# attiny1634_bo.net
KiCad netlist of a schematic drawn in EAGLE
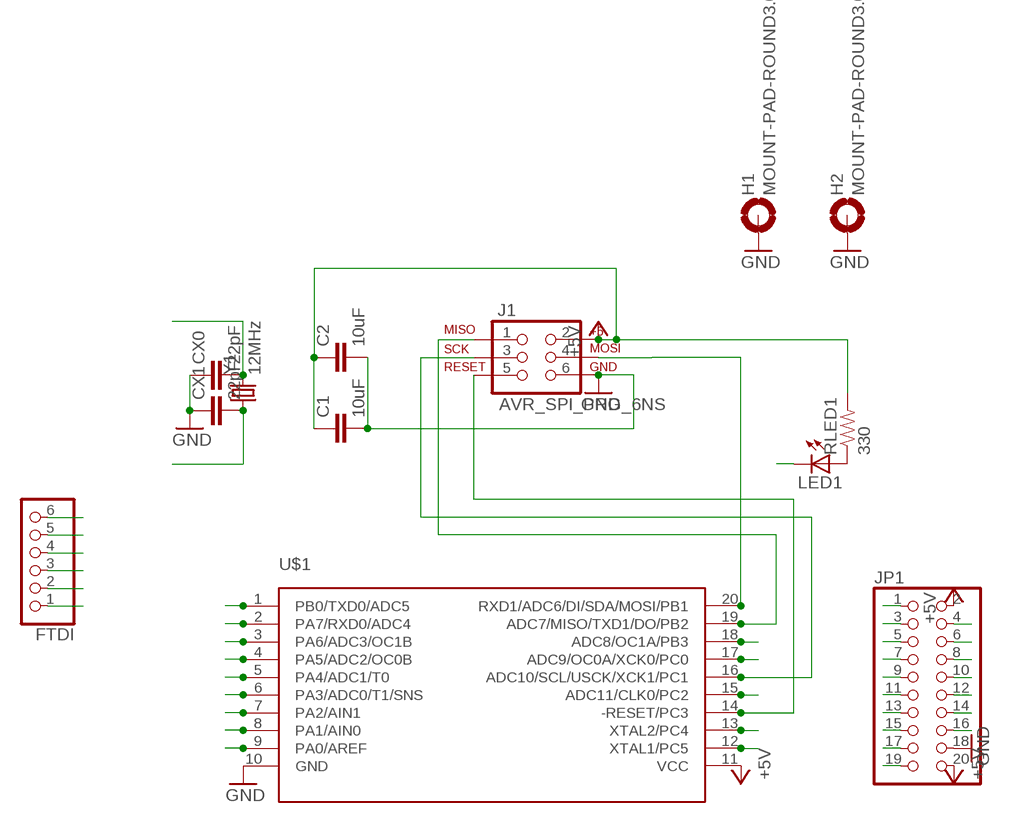
[diagram p0: schematic, sheet 1]

(export (version "E")
  (design (tool "Eeschema 10.0.6"))
  (components
    (comp (ref "C1")
      (value "10uF")
      (footprint "eagle-import:C0805")
      (libsource (lib "eagle-import") (part "C-EUC0805"))
    )
    (comp (ref "C2")
      (value "10uF")
      (footprint "eagle-import:C0805")
      (libsource (lib "eagle-import") (part "C-EUC0805"))
    )
    (comp (ref "CX0")
      (value "22pF")
      (footprint "eagle-import:C0603")
      (libsource (lib "eagle-import") (part "C-EUC0603"))
    )
    (comp (ref "CX1")
      (value "22pF")
      (footprint "eagle-import:C0603")
      (libsource (lib "eagle-import") (part "C-EUC0603"))
    )
    (comp (ref "FTDI")
      (value "PINHD-1X6")
      (footprint "eagle-import:1X06")
      (libsource (lib "eagle-import") (part "PINHD-1X6"))
    )
    (comp (ref "H1")
      (value "MOUNT-PAD-ROUND3.0")
      (footprint "eagle-import:3,0-PAD")
      (libsource (lib "eagle-import") (part "MOUNT-PAD-ROUND3.0"))
    )
    (comp (ref "H2")
      (value "MOUNT-PAD-ROUND3.0")
      (footprint "eagle-import:3,0-PAD")
      (libsource (lib "eagle-import") (part "MOUNT-PAD-ROUND3.0"))
    )
    (comp (ref "J1")
      (value "AVR_SPI_PRG_6NS")
      (footprint "eagle-import:2X3-NS")
      (libsource (lib "eagle-import") (part "AVR_SPI_PRG_6NS"))
    )
    (comp (ref "JP1")
      (value "PINHD-2X10")
      (footprint "eagle-import:2X10")
      (libsource (lib "eagle-import") (part "PINHD-2X10"))
    )
    (comp (ref "LED1")
      (value "LED0603")
      (footprint "eagle-import:LED-0603")
      (libsource (lib "eagle-import") (part "LED0603"))
    )
    (comp (ref "RLED1")
      (value "330")
      (footprint "eagle-import:0603-RES")
      (libsource (lib "eagle-import") (part "RESISTOR0603-RES"))
    )
    (comp (ref "U$1")
      (value "ATTINY1634")
      (footprint "eagle-import:SOIC20")
      (libsource (lib "eagle-import") (part "ATTINY1634"))
    )
    (comp (ref "Y1")
      (value "12MHz")
      (footprint "eagle-import:CRYSTAL-SMD-5X3")
      (libsource (lib "eagle-import") (part "CRYSTAL5X3"))
    )
  )
  (nets
    (net (code "1") (name "+5V") (class "Default")
      (node (ref "C1") (pin "1") (pinfunction "1_1") (pintype "passive"))
      (node (ref "C2") (pin "1") (pinfunction "1_1") (pintype "passive"))
      (node (ref "FTDI") (pin "3") (pinfunction "3_3") (pintype "passive"))
      (node (ref "J1") (pin "2") (pinfunction "2_2") (pintype "passive"))
      (node (ref "JP1") (pin "2") (pinfunction "2_2") (pintype "passive"))
      (node (ref "JP1") (pin "20") (pinfunction "20_20") (pintype "passive"))
      (node (ref "RLED1") (pin "2") (pinfunction "2_2") (pintype "passive"))
      (node (ref "U$1") (pin "11") (pinfunction "VCC_11") (pintype "power_in"))
    )
    (net (code "2") (name "/PA0") (class "Default")
      (node (ref "JP1") (pin "5") (pinfunction "5_5") (pintype "passive"))
      (node (ref "U$1") (pin "9") (pinfunction "PA0/AREF_9") (pintype "bidirectional"))
    )
    (net (code "3") (name "/PA1") (class "Default")
      (node (ref "JP1") (pin "7") (pinfunction "7_7") (pintype "passive"))
      (node (ref "U$1") (pin "8") (pinfunction "PA1/AIN0_8") (pintype "bidirectional"))
    )
    (net (code "4") (name "/PA2") (class "Default")
      (node (ref "JP1") (pin "9") (pinfunction "9_9") (pintype "passive"))
      (node (ref "U$1") (pin "7") (pinfunction "PA2/AIN1_7") (pintype "bidirectional"))
    )
    (net (code "5") (name "/PA3") (class "Default")
      (node (ref "JP1") (pin "11") (pinfunction "11_11") (pintype "passive"))
      (node (ref "U$1") (pin "6") (pinfunction "PA3/ADC0/T1/SNS_6") (pintype "bidirectional"))
    )
    (net (code "6") (name "/PA4") (class "Default")
      (node (ref "JP1") (pin "13") (pinfunction "13_13") (pintype "passive"))
      (node (ref "U$1") (pin "5") (pinfunction "PA4/ADC1/T0_5") (pintype "bidirectional"))
    )
    (net (code "7") (name "/PA5") (class "Default")
      (node (ref "JP1") (pin "15") (pinfunction "15_15") (pintype "passive"))
      (node (ref "U$1") (pin "4") (pinfunction "PA5/ADC2/OC0B_4") (pintype "bidirectional"))
    )
    (net (code "8") (name "/PA6") (class "Default")
      (node (ref "JP1") (pin "17") (pinfunction "17_17") (pintype "passive"))
      (node (ref "U$1") (pin "3") (pinfunction "PA6/ADC3/OC1B_3") (pintype "bidirectional"))
    )
    (net (code "9") (name "/PA7{slash}RX0") (class "Default")
      (node (ref "FTDI") (pin "4") (pinfunction "4_4") (pintype "passive"))
      (node (ref "JP1") (pin "19") (pinfunction "19_19") (pintype "passive"))
      (node (ref "U$1") (pin "2") (pinfunction "PA7/RXD0/ADC4_2") (pintype "bidirectional"))
    )
    (net (code "10") (name "/PB0{slash}TXD0") (class "Default")
      (node (ref "FTDI") (pin "5") (pinfunction "5_5") (pintype "passive"))
      (node (ref "JP1") (pin "16") (pinfunction "16_16") (pintype "passive"))
      (node (ref "U$1") (pin "1") (pinfunction "PB0/TXD0/ADC5_1") (pintype "bidirectional"))
    )
    (net (code "11") (name "/PB1{slash}MOSI{slash}ADC6") (class "Default")
      (node (ref "J1") (pin "4") (pinfunction "4_4") (pintype "passive"))
      (node (ref "JP1") (pin "14") (pinfunction "14_14") (pintype "passive"))
      (node (ref "U$1") (pin "20") (pinfunction "RXD1/ADC6/DI/SDA/MOSI/PB1_20") (pintype "bidirectional"))
    )
    (net (code "12") (name "/PB2{slash}ADC7{slash}TX1") (class "Default")
      (node (ref "J1") (pin "1") (pinfunction "1_1") (pintype "passive"))
      (node (ref "JP1") (pin "12") (pinfunction "12_12") (pintype "passive"))
      (node (ref "U$1") (pin "19") (pinfunction "ADC7/MISO/TXD1/DO/PB2_19") (pintype "bidirectional"))
    )
    (net (code "13") (name "/PB3{slash}ADC8{slash}OC1A") (class "Default")
      (node (ref "JP1") (pin "10") (pinfunction "10_10") (pintype "passive"))
      (node (ref "U$1") (pin "18") (pinfunction "ADC8/OC1A/PB3_18") (pintype "bidirectional"))
    )
    (net (code "14") (name "/PC0{slash}ADC9{slash}OC0A") (class "Default")
      (node (ref "JP1") (pin "8") (pinfunction "8_8") (pintype "passive"))
      (node (ref "LED1") (pin "C") (pinfunction "C_C") (pintype "passive"))
      (node (ref "U$1") (pin "17") (pinfunction "ADC9/OC0A/XCK0/PC0_17") (pintype "bidirectional"))
    )
    (net (code "15") (name "/PC1{slash}SCL{slash}ADC10") (class "Default")
      (node (ref "J1") (pin "3") (pinfunction "3_3") (pintype "passive"))
      (node (ref "JP1") (pin "1") (pinfunction "1_1") (pintype "passive"))
      (node (ref "U$1") (pin "16") (pinfunction "ADC10/SCL/USCK/XCK1/PC1_16") (pintype "bidirectional"))
    )
    (net (code "16") (name "/PC2{slash}ADC11") (class "Default")
      (node (ref "JP1") (pin "3") (pinfunction "3_3") (pintype "passive"))
      (node (ref "U$1") (pin "15") (pinfunction "ADC11/CLK0/PC2_15") (pintype "bidirectional"))
    )
    (net (code "17") (name "/PC3{slash}-RESET") (class "Default")
      (node (ref "FTDI") (pin "6") (pinfunction "6_6") (pintype "passive"))
      (node (ref "J1") (pin "5") (pinfunction "5_5") (pintype "passive"))
      (node (ref "U$1") (pin "14") (pinfunction "-RESET/PC3_14") (pintype "bidirectional"))
    )
    (net (code "18") (name "/PC4{slash}XTAL2") (class "Default")
      (node (ref "CX0") (pin "2") (pinfunction "2_2") (pintype "passive"))
      (node (ref "JP1") (pin "6") (pinfunction "6_6") (pintype "passive"))
      (node (ref "U$1") (pin "13") (pinfunction "XTAL2/PC4_13") (pintype "bidirectional"))
      (node (ref "Y1") (pin "3") (pinfunction "2_3") (pintype "passive"))
    )
    (net (code "19") (name "/PC5{slash}XTAL1") (class "Default")
      (node (ref "CX1") (pin "2") (pinfunction "2_2") (pintype "passive"))
      (node (ref "JP1") (pin "4") (pinfunction "4_4") (pintype "passive"))
      (node (ref "U$1") (pin "12") (pinfunction "XTAL1/PC5_12") (pintype "bidirectional"))
      (node (ref "Y1") (pin "1") (pinfunction "1_1") (pintype "passive"))
    )
    (net (code "20") (name "GND") (class "Default")
      (node (ref "C1") (pin "2") (pinfunction "2_2") (pintype "passive"))
      (node (ref "C2") (pin "2") (pinfunction "2_2") (pintype "passive"))
      (node (ref "CX0") (pin "1") (pinfunction "1_1") (pintype "passive"))
      (node (ref "CX1") (pin "1") (pinfunction "1_1") (pintype "passive"))
      (node (ref "FTDI") (pin "1") (pinfunction "1_1") (pintype "passive"))
      (node (ref "H1") (pin "B3,0") (pinfunction "MOUNT_B3,0") (pintype "passive"))
      (node (ref "H2") (pin "B3,0") (pinfunction "MOUNT_B3,0") (pintype "passive"))
      (node (ref "J1") (pin "6") (pinfunction "6_6") (pintype "passive"))
      (node (ref "JP1") (pin "18") (pinfunction "18_18") (pintype "passive"))
      (node (ref "U$1") (pin "10") (pinfunction "GND_10") (pintype "power_in"))
    )
    (net (code "21") (name "Net-(LED1-PadA)") (class "Default")
      (node (ref "LED1") (pin "A") (pinfunction "A_A") (pintype "passive"))
      (node (ref "RLED1") (pin "1") (pinfunction "1_1") (pintype "passive"))
    )
    (net (code "22") (name "unconnected-(FTDI-Pad2)") (class "Default")
      (node (ref "FTDI") (pin "2") (pinfunction "2_2") (pintype "passive"))
    )
  )
)
